# Z80Console0002.net
KiCad netlist of a schematic drawn in Altium Designer
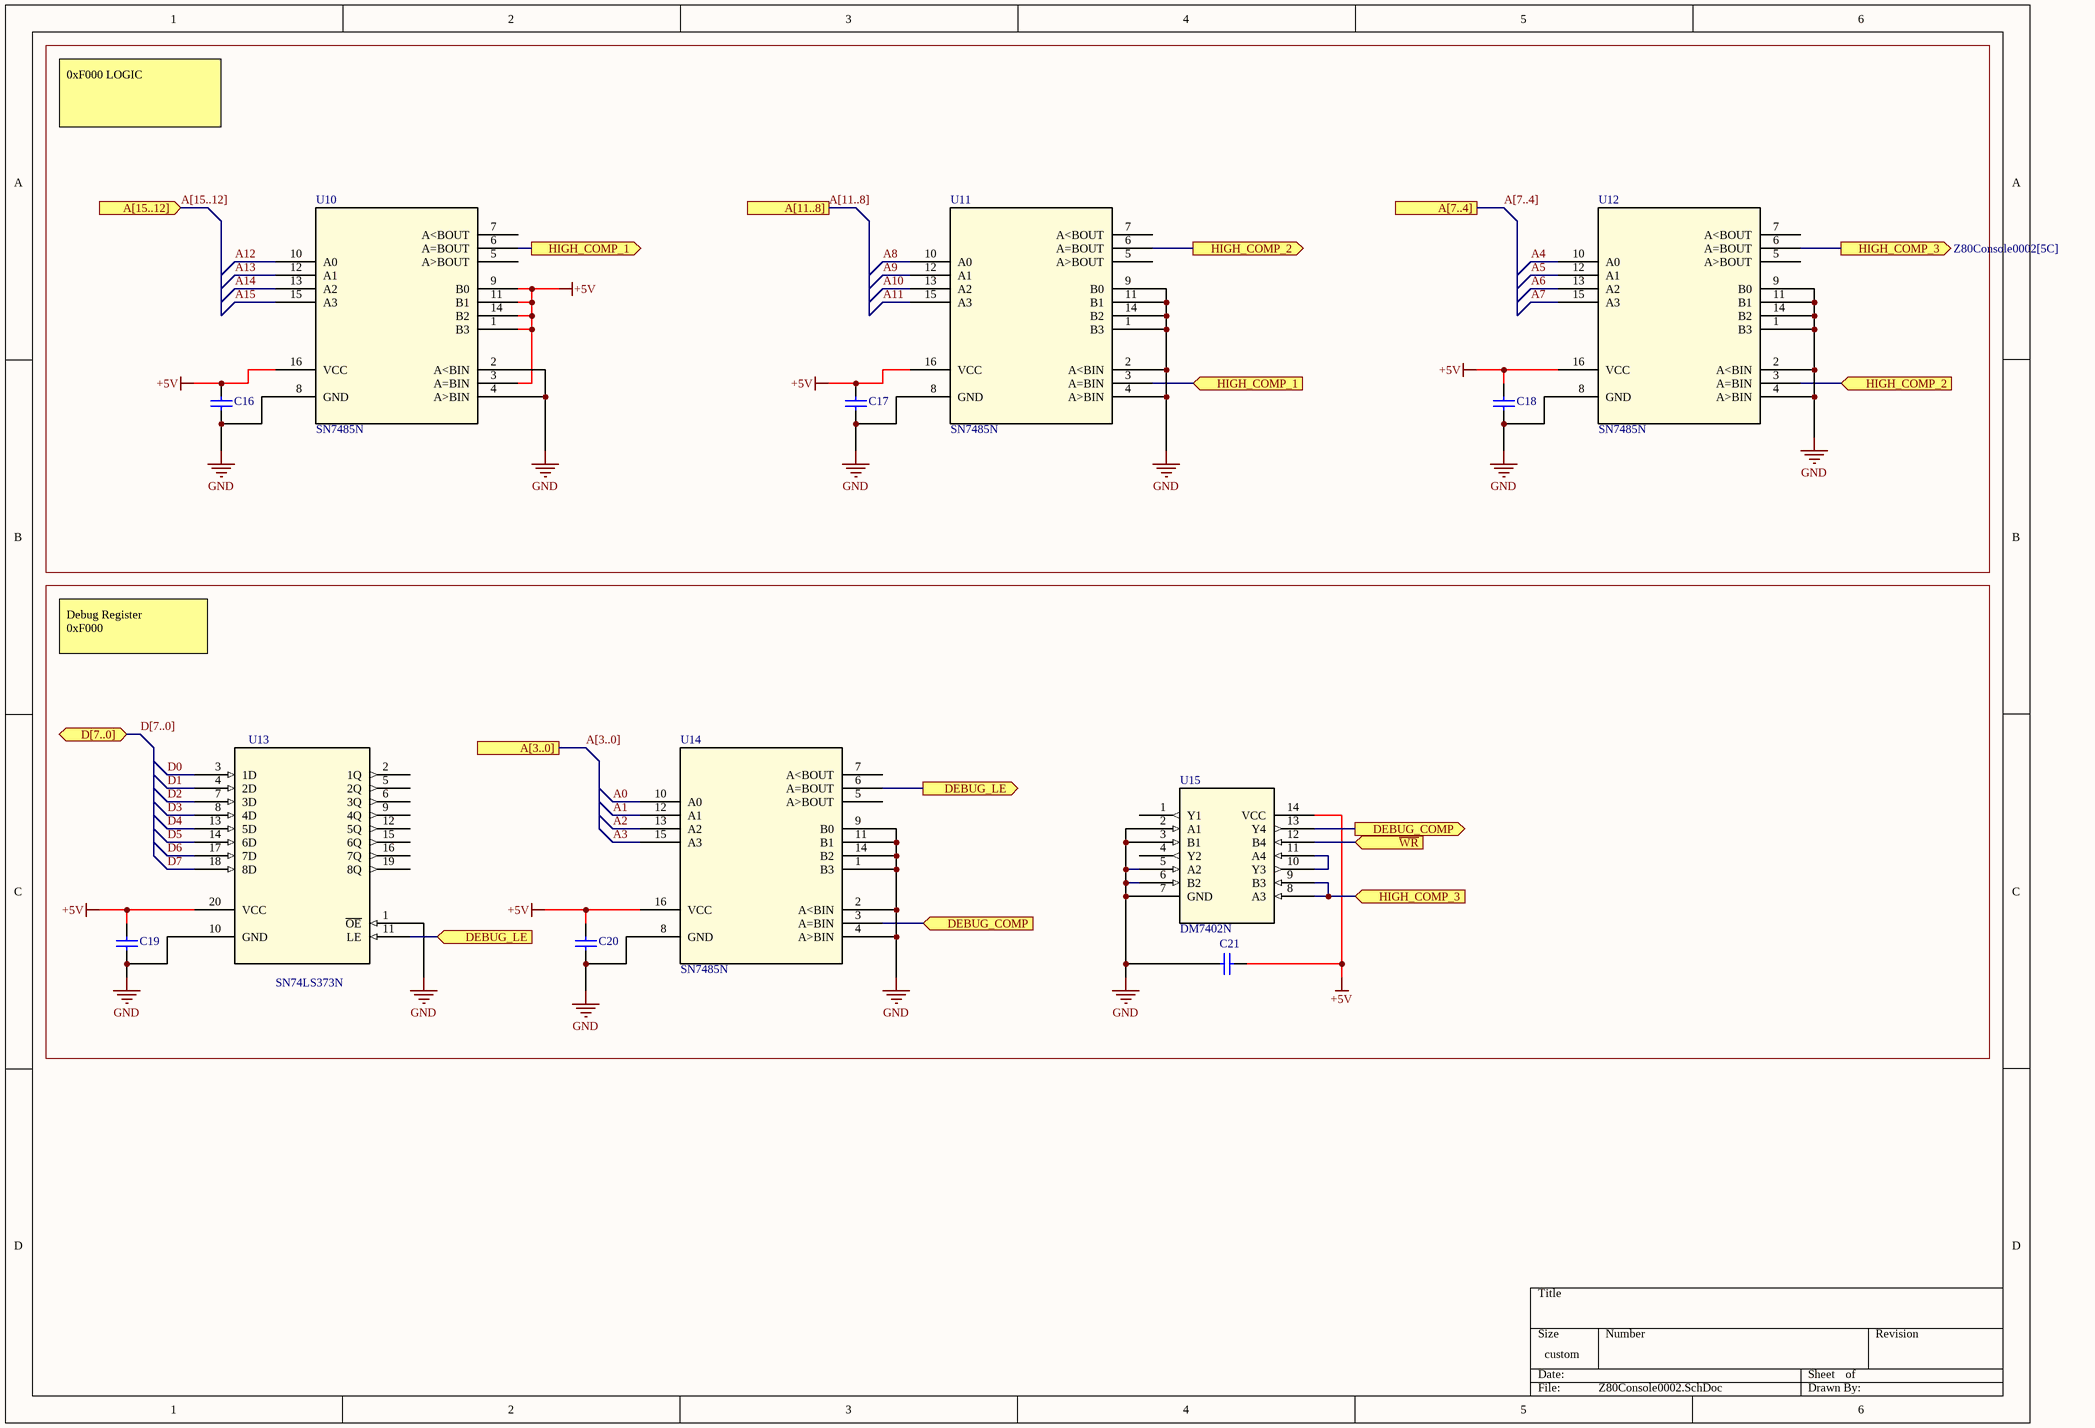
[diagram p0: Z80Console0002.SchDoc]

(export (version "E")
  (design (tool "Eeschema 10.0.6"))
  (components
    (comp (ref "C16")
      (value "CAP")
      (footprint "CAPC0603(1608)100_N")
      (libsource (lib "Passive SMD") (part "CAP"))
    )
    (comp (ref "C17")
      (value "CAP")
      (footprint "CAPC0603(1608)100_N")
      (libsource (lib "Passive SMD") (part "CAP"))
    )
    (comp (ref "C18")
      (value "CAP")
      (footprint "CAPC0603(1608)100_N")
      (libsource (lib "Passive SMD") (part "CAP"))
    )
    (comp (ref "C19")
      (value "CAP")
      (footprint "CAPC0603(1608)100_N")
      (libsource (lib "Passive SMD") (part "CAP"))
    )
    (comp (ref "C20")
      (value "CAP")
      (footprint "CAPC0603(1608)100_N")
      (libsource (lib "Passive SMD") (part "CAP"))
    )
    (comp (ref "C21")
      (value "CAP")
      (footprint "CAPC0603(1608)100_N")
      (libsource (lib "Passive SMD") (part "CAP"))
    )
    (comp (ref "U10")
      (value "SN7485N")
      (footprint "DIP16_300")
      (description "4-bit Magnitude Comparator")
      (fields (field (name "COPYRIGHT") "Copyright (C) 2025 Ultra Librarian. All rights reserved."))
      (libsource (lib "Z80Console") (part "SN7485N"))
    )
    (comp (ref "U11")
      (value "SN7485N")
      (footprint "DIP16_300")
      (description "4-bit Magnitude Comparator")
      (fields (field (name "COPYRIGHT") "Copyright (C) 2025 Ultra Librarian. All rights reserved."))
      (libsource (lib "Z80Console") (part "SN7485N"))
    )
    (comp (ref "U12")
      (value "SN7485N")
      (footprint "DIP16_300")
      (description "4-bit Magnitude Comparator")
      (fields (field (name "COPYRIGHT") "Copyright (C) 2025 Ultra Librarian. All rights reserved."))
      (libsource (lib "Z80Console") (part "SN7485N"))
    )
    (comp (ref "U13")
      (value "SN74LS373N")
      (footprint "N20")
      (description "Octal D-type Transparent Latches with 3-state Outputs 20-PDIP 0 to 70")
      (fields (field (name "COPYRIGHT") "Copyright (C) 2025 Ultra Librarian. All rights reserved."))
      (libsource (lib "Z80Console") (part "SN74LS373N"))
    )
    (comp (ref "U14")
      (value "SN7485N")
      (footprint "DIP16_300")
      (description "4-bit Magnitude Comparator")
      (fields (field (name "COPYRIGHT") "Copyright (C) 2025 Ultra Librarian. All rights reserved."))
      (libsource (lib "Z80Console") (part "SN7485N"))
    )
    (comp (ref "U15")
      (value "DM7402N")
      (footprint "PDIP14_19P56X6P35_ONS")
      (description "NOR Gate")
      (fields (field (name "COPYRIGHT") "Copyright (C) 2025 Ultra Librarian. All rights reserved."))
      (libsource (lib "Z80Console") (part "DM7402N"))
    )
  )
  (nets
    (net (code "1") (name "+5V") (class "Default")
      (node (ref "C16") (pin "2") (pinfunction "2_2") (pintype "passive"))
      (node (ref "C17") (pin "2") (pinfunction "2_2") (pintype "passive"))
      (node (ref "C18") (pin "2") (pinfunction "2_2") (pintype "passive"))
      (node (ref "C19") (pin "2") (pinfunction "2_2") (pintype "passive"))
      (node (ref "C20") (pin "2") (pinfunction "2_2") (pintype "passive"))
      (node (ref "C21") (pin "2") (pinfunction "2_2") (pintype "passive"))
      (node (ref "U10") (pin "1") (pinfunction "B3_1") (pintype "passive"))
      (node (ref "U10") (pin "11") (pinfunction "B1_11") (pintype "passive"))
      (node (ref "U10") (pin "14") (pinfunction "B2_14") (pintype "passive"))
      (node (ref "U10") (pin "16") (pinfunction "VCC_16") (pintype "passive"))
      (node (ref "U10") (pin "3") (pinfunction "A=BIN_3") (pintype "passive"))
      (node (ref "U10") (pin "9") (pinfunction "B0_9") (pintype "passive"))
      (node (ref "U11") (pin "16") (pinfunction "VCC_16") (pintype "passive"))
      (node (ref "U12") (pin "16") (pinfunction "VCC_16") (pintype "passive"))
      (node (ref "U13") (pin "20") (pinfunction "VCC_20") (pintype "power_in"))
      (node (ref "U14") (pin "16") (pinfunction "VCC_16") (pintype "passive"))
      (node (ref "U15") (pin "14") (pinfunction "VCC_14") (pintype "power_in"))
    )
    (net (code "2") (name "/A0") (class "Default")
      (node (ref "U14") (pin "10") (pinfunction "A0_10") (pintype "passive"))
    )
    (net (code "3") (name "/A1") (class "Default")
      (node (ref "U14") (pin "12") (pinfunction "A1_12") (pintype "passive"))
    )
    (net (code "4") (name "/A2") (class "Default")
      (node (ref "U14") (pin "13") (pinfunction "A2_13") (pintype "passive"))
    )
    (net (code "5") (name "/A3") (class "Default")
      (node (ref "U14") (pin "15") (pinfunction "A3_15") (pintype "passive"))
    )
    (net (code "6") (name "/A4") (class "Default")
      (node (ref "U12") (pin "10") (pinfunction "A0_10") (pintype "passive"))
    )
    (net (code "7") (name "/A5") (class "Default")
      (node (ref "U12") (pin "12") (pinfunction "A1_12") (pintype "passive"))
    )
    (net (code "8") (name "/A6") (class "Default")
      (node (ref "U12") (pin "13") (pinfunction "A2_13") (pintype "passive"))
    )
    (net (code "9") (name "/A7") (class "Default")
      (node (ref "U12") (pin "15") (pinfunction "A3_15") (pintype "passive"))
    )
    (net (code "10") (name "/A8") (class "Default")
      (node (ref "U11") (pin "10") (pinfunction "A0_10") (pintype "passive"))
    )
    (net (code "11") (name "/A9") (class "Default")
      (node (ref "U11") (pin "12") (pinfunction "A1_12") (pintype "passive"))
    )
    (net (code "12") (name "/A10") (class "Default")
      (node (ref "U11") (pin "13") (pinfunction "A2_13") (pintype "passive"))
    )
    (net (code "13") (name "/A11") (class "Default")
      (node (ref "U11") (pin "15") (pinfunction "A3_15") (pintype "passive"))
    )
    (net (code "14") (name "/A12") (class "Default")
      (node (ref "U10") (pin "10") (pinfunction "A0_10") (pintype "passive"))
    )
    (net (code "15") (name "/A13") (class "Default")
      (node (ref "U10") (pin "12") (pinfunction "A1_12") (pintype "passive"))
    )
    (net (code "16") (name "/A14") (class "Default")
      (node (ref "U10") (pin "13") (pinfunction "A2_13") (pintype "passive"))
    )
    (net (code "17") (name "/A15") (class "Default")
      (node (ref "U10") (pin "15") (pinfunction "A3_15") (pintype "passive"))
    )
    (net (code "22") (name "/D0") (class "Default")
      (node (ref "U13") (pin "3") (pinfunction "1D_3") (pintype "input"))
    )
    (net (code "23") (name "/D1") (class "Default")
      (node (ref "U13") (pin "4") (pinfunction "2D_4") (pintype "input"))
    )
    (net (code "24") (name "/D2") (class "Default")
      (node (ref "U13") (pin "7") (pinfunction "3D_7") (pintype "input"))
    )
    (net (code "25") (name "/D3") (class "Default")
      (node (ref "U13") (pin "8") (pinfunction "4D_8") (pintype "input"))
    )
    (net (code "26") (name "/D4") (class "Default")
      (node (ref "U13") (pin "13") (pinfunction "5D_13") (pintype "input"))
    )
    (net (code "27") (name "/D5") (class "Default")
      (node (ref "U13") (pin "14") (pinfunction "6D_14") (pintype "input"))
    )
    (net (code "28") (name "/D6") (class "Default")
      (node (ref "U13") (pin "17") (pinfunction "7D_17") (pintype "input"))
    )
    (net (code "29") (name "/D7") (class "Default")
      (node (ref "U13") (pin "18") (pinfunction "8D_18") (pintype "input"))
    )
    (net (code "30") (name "/DEBUG_COMP") (class "Default")
      (node (ref "U14") (pin "3") (pinfunction "A=BIN_3") (pintype "passive"))
      (node (ref "U15") (pin "13") (pinfunction "Y4_13") (pintype "output"))
    )
    (net (code "31") (name "/DEBUG_LE") (class "Default")
      (node (ref "U13") (pin "11") (pinfunction "LE_11") (pintype "input"))
      (node (ref "U14") (pin "6") (pinfunction "A=BOUT_6") (pintype "passive"))
    )
    (net (code "33") (name "/HIGH_COMP_1") (class "Default")
      (node (ref "U10") (pin "6") (pinfunction "A=BOUT_6") (pintype "passive"))
      (node (ref "U11") (pin "3") (pinfunction "A=BIN_3") (pintype "passive"))
    )
    (net (code "34") (name "/HIGH_COMP_2") (class "Default")
      (node (ref "U11") (pin "6") (pinfunction "A=BOUT_6") (pintype "passive"))
      (node (ref "U12") (pin "3") (pinfunction "A=BIN_3") (pintype "passive"))
    )
    (net (code "35") (name "/HIGH_COMP_3") (class "Default")
      (node (ref "U12") (pin "6") (pinfunction "A=BOUT_6") (pintype "passive"))
      (node (ref "U15") (pin "8") (pinfunction "A3_8") (pintype "input"))
      (node (ref "U15") (pin "9") (pinfunction "B3_9") (pintype "input"))
    )
    (net (code "36") (name "/WR") (class "Default")
      (node (ref "U15") (pin "12") (pinfunction "B4_12") (pintype "input"))
    )
    (net (code "37") (name "GND") (class "Default")
      (node (ref "C16") (pin "1") (pinfunction "1_1") (pintype "passive"))
      (node (ref "C17") (pin "1") (pinfunction "1_1") (pintype "passive"))
      (node (ref "C18") (pin "1") (pinfunction "1_1") (pintype "passive"))
      (node (ref "C19") (pin "1") (pinfunction "1_1") (pintype "passive"))
      (node (ref "C20") (pin "1") (pinfunction "1_1") (pintype "passive"))
      (node (ref "C21") (pin "1") (pinfunction "1_1") (pintype "passive"))
      (node (ref "U10") (pin "2") (pinfunction "A<BIN_2") (pintype "passive"))
      (node (ref "U10") (pin "4") (pinfunction "A>BIN_4") (pintype "passive"))
      (node (ref "U10") (pin "8") (pinfunction "GND_8") (pintype "passive"))
      (node (ref "U11") (pin "1") (pinfunction "B3_1") (pintype "passive"))
      (node (ref "U11") (pin "11") (pinfunction "B1_11") (pintype "passive"))
      (node (ref "U11") (pin "14") (pinfunction "B2_14") (pintype "passive"))
      (node (ref "U11") (pin "2") (pinfunction "A<BIN_2") (pintype "passive"))
      (node (ref "U11") (pin "4") (pinfunction "A>BIN_4") (pintype "passive"))
      (node (ref "U11") (pin "8") (pinfunction "GND_8") (pintype "passive"))
      (node (ref "U11") (pin "9") (pinfunction "B0_9") (pintype "passive"))
      (node (ref "U12") (pin "1") (pinfunction "B3_1") (pintype "passive"))
      (node (ref "U12") (pin "11") (pinfunction "B1_11") (pintype "passive"))
      (node (ref "U12") (pin "14") (pinfunction "B2_14") (pintype "passive"))
      (node (ref "U12") (pin "2") (pinfunction "A<BIN_2") (pintype "passive"))
      (node (ref "U12") (pin "4") (pinfunction "A>BIN_4") (pintype "passive"))
      (node (ref "U12") (pin "8") (pinfunction "GND_8") (pintype "passive"))
      (node (ref "U12") (pin "9") (pinfunction "B0_9") (pintype "passive"))
      (node (ref "U13") (pin "1") (pinfunction "OE_1") (pintype "input"))
      (node (ref "U13") (pin "10") (pinfunction "GND_10") (pintype "power_in"))
      (node (ref "U14") (pin "1") (pinfunction "B3_1") (pintype "passive"))
      (node (ref "U14") (pin "11") (pinfunction "B1_11") (pintype "passive"))
      (node (ref "U14") (pin "14") (pinfunction "B2_14") (pintype "passive"))
      (node (ref "U14") (pin "2") (pinfunction "A<BIN_2") (pintype "passive"))
      (node (ref "U14") (pin "4") (pinfunction "A>BIN_4") (pintype "passive"))
      (node (ref "U14") (pin "8") (pinfunction "GND_8") (pintype "passive"))
      (node (ref "U14") (pin "9") (pinfunction "B0_9") (pintype "passive"))
      (node (ref "U15") (pin "2") (pinfunction "A1_2") (pintype "input"))
      (node (ref "U15") (pin "3") (pinfunction "B1_3") (pintype "input"))
      (node (ref "U15") (pin "5") (pinfunction "A2_5") (pintype "input"))
      (node (ref "U15") (pin "6") (pinfunction "B2_6") (pintype "input"))
      (node (ref "U15") (pin "7") (pinfunction "GND_7") (pintype "power_in"))
    )
    (net (code "38") (name "Net-(U15-A4)") (class "Default")
      (node (ref "U15") (pin "10") (pinfunction "Y3_10") (pintype "output"))
      (node (ref "U15") (pin "11") (pinfunction "A4_11") (pintype "input"))
    )
    (net (code "39") (name "unconnected-(U10-A<BOUT-Pad7)") (class "Default")
      (node (ref "U10") (pin "7") (pinfunction "A<BOUT_7") (pintype "passive"))
    )
    (net (code "40") (name "unconnected-(U10-A>BOUT-Pad5)") (class "Default")
      (node (ref "U10") (pin "5") (pinfunction "A>BOUT_5") (pintype "passive"))
    )
    (net (code "41") (name "unconnected-(U11-A<BOUT-Pad7)") (class "Default")
      (node (ref "U11") (pin "7") (pinfunction "A<BOUT_7") (pintype "passive"))
    )
    (net (code "42") (name "unconnected-(U11-A>BOUT-Pad5)") (class "Default")
      (node (ref "U11") (pin "5") (pinfunction "A>BOUT_5") (pintype "passive"))
    )
    (net (code "43") (name "unconnected-(U12-A<BOUT-Pad7)") (class "Default")
      (node (ref "U12") (pin "7") (pinfunction "A<BOUT_7") (pintype "passive"))
    )
    (net (code "44") (name "unconnected-(U12-A>BOUT-Pad5)") (class "Default")
      (node (ref "U12") (pin "5") (pinfunction "A>BOUT_5") (pintype "passive"))
    )
    (net (code "45") (name "unconnected-(U13-1Q-Pad2)") (class "Default")
      (node (ref "U13") (pin "2") (pinfunction "1Q_2") (pintype "output"))
    )
    (net (code "46") (name "unconnected-(U13-2Q-Pad5)") (class "Default")
      (node (ref "U13") (pin "5") (pinfunction "2Q_5") (pintype "output"))
    )
    (net (code "47") (name "unconnected-(U13-3Q-Pad6)") (class "Default")
      (node (ref "U13") (pin "6") (pinfunction "3Q_6") (pintype "output"))
    )
    (net (code "48") (name "unconnected-(U13-4Q-Pad9)") (class "Default")
      (node (ref "U13") (pin "9") (pinfunction "4Q_9") (pintype "output"))
    )
    (net (code "49") (name "unconnected-(U13-5Q-Pad12)") (class "Default")
      (node (ref "U13") (pin "12") (pinfunction "5Q_12") (pintype "output"))
    )
    (net (code "50") (name "unconnected-(U13-6Q-Pad15)") (class "Default")
      (node (ref "U13") (pin "15") (pinfunction "6Q_15") (pintype "output"))
    )
    (net (code "51") (name "unconnected-(U13-7Q-Pad16)") (class "Default")
      (node (ref "U13") (pin "16") (pinfunction "7Q_16") (pintype "output"))
    )
    (net (code "52") (name "unconnected-(U13-8Q-Pad19)") (class "Default")
      (node (ref "U13") (pin "19") (pinfunction "8Q_19") (pintype "output"))
    )
    (net (code "53") (name "unconnected-(U14-A<BOUT-Pad7)") (class "Default")
      (node (ref "U14") (pin "7") (pinfunction "A<BOUT_7") (pintype "passive"))
    )
    (net (code "54") (name "unconnected-(U14-A>BOUT-Pad5)") (class "Default")
      (node (ref "U14") (pin "5") (pinfunction "A>BOUT_5") (pintype "passive"))
    )
    (net (code "55") (name "unconnected-(U15-Y1-Pad1)") (class "Default")
      (node (ref "U15") (pin "1") (pinfunction "Y1_1") (pintype "output"))
    )
    (net (code "56") (name "unconnected-(U15-Y2-Pad4)") (class "Default")
      (node (ref "U15") (pin "4") (pinfunction "Y2_4") (pintype "output"))
    )
  )
)
